# Analog.net
KiCad netlist of a schematic drawn in Altium Designer
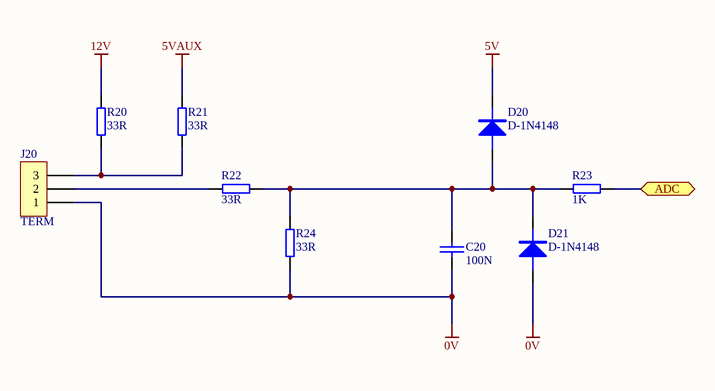
[diagram p0: Analog.SchDoc]

(export (version "E")
  (design (tool "Eeschema 10.0.6"))
  (components
    (comp (ref "C20")
      (value "100N")
      (footprint "AXIAL02")
      (description "CAPACITOR")
      (libsource (lib "SSR") (part "C-B100N"))
    )
    (comp (ref "D20")
      (value "D-1N4148")
      (footprint "DO35S")
      (description "1N4148")
      (libsource (lib "SSR") (part "D-1N4148"))
    )
    (comp (ref "D21")
      (value "D-1N4148")
      (footprint "DO35S")
      (description "1N4148")
      (libsource (lib "SSR") (part "D-1N4148"))
    )
    (comp (ref "J20")
      (value "TERM")
      (footprint "MKD500S3")
      (description "CONNECTOR")
      (libsource (lib "SSR") (part "J-SCR-3"))
    )
    (comp (ref "R20")
      (value "33R")
      (footprint "AXIAL04")
      (description "RESISTOR")
      (libsource (lib "SSR") (part "R-A33R"))
    )
    (comp (ref "R21")
      (value "33R")
      (footprint "AXIAL04")
      (description "RESISTOR")
      (libsource (lib "SSR") (part "R-A33R"))
    )
    (comp (ref "R22")
      (value "33R")
      (footprint "AXIAL04")
      (description "RESISTOR")
      (libsource (lib "SSR") (part "R-A33R"))
    )
    (comp (ref "R23")
      (value "1K")
      (footprint "AXIAL04")
      (description "RESISTOR")
      (libsource (lib "SSR") (part "R-A1K"))
    )
    (comp (ref "R24")
      (value "33R")
      (footprint "AXIAL04")
      (description "RESISTOR")
      (libsource (lib "SSR") (part "R-A33R"))
    )
  )
  (nets
    (net (code "1") (name "/ADC") (class "Default")
      (node (ref "R23") (pin "2") (pinfunction "2_2") (pintype "passive"))
    )
    (net (code "2") (name "0V") (class "Default")
      (node (ref "C20") (pin "2") (pinfunction "2_2") (pintype "passive"))
      (node (ref "D21") (pin "1") (pinfunction "A_1") (pintype "passive"))
      (node (ref "J20") (pin "1") (pinfunction "1_1") (pintype "passive"))
      (node (ref "R24") (pin "1") (pinfunction "1_1") (pintype "passive"))
    )
    (net (code "3") (name "5V") (class "Default")
      (node (ref "D20") (pin "2") (pinfunction "K_2") (pintype "passive"))
    )
    (net (code "4") (name "5VAUX") (class "Default")
      (node (ref "R21") (pin "2") (pinfunction "2_2") (pintype "passive"))
    )
    (net (code "5") (name "12V") (class "Default")
      (node (ref "R20") (pin "2") (pinfunction "2_2") (pintype "passive"))
    )
    (net (code "6") (name "Net-(D20-A)") (class "Default")
      (node (ref "C20") (pin "1") (pinfunction "1_1") (pintype "passive"))
      (node (ref "D20") (pin "1") (pinfunction "A_1") (pintype "passive"))
      (node (ref "D21") (pin "2") (pinfunction "K_2") (pintype "passive"))
      (node (ref "R22") (pin "1") (pinfunction "1_1") (pintype "passive"))
      (node (ref "R23") (pin "1") (pinfunction "1_1") (pintype "passive"))
      (node (ref "R24") (pin "2") (pinfunction "2_2") (pintype "passive"))
    )
    (net (code "7") (name "Net-(J20-Pad2)") (class "Default")
      (node (ref "J20") (pin "2") (pinfunction "2_2") (pintype "passive"))
      (node (ref "R22") (pin "2") (pinfunction "2_2") (pintype "passive"))
    )
    (net (code "8") (name "Net-(J20-Pad3)") (class "Default")
      (node (ref "J20") (pin "3") (pinfunction "3_3") (pintype "passive"))
      (node (ref "R20") (pin "1") (pinfunction "1_1") (pintype "passive"))
      (node (ref "R21") (pin "1") (pinfunction "1_1") (pintype "passive"))
    )
  )
)
